# Core.net
KiCad netlist of a schematic drawn in Altium Designer
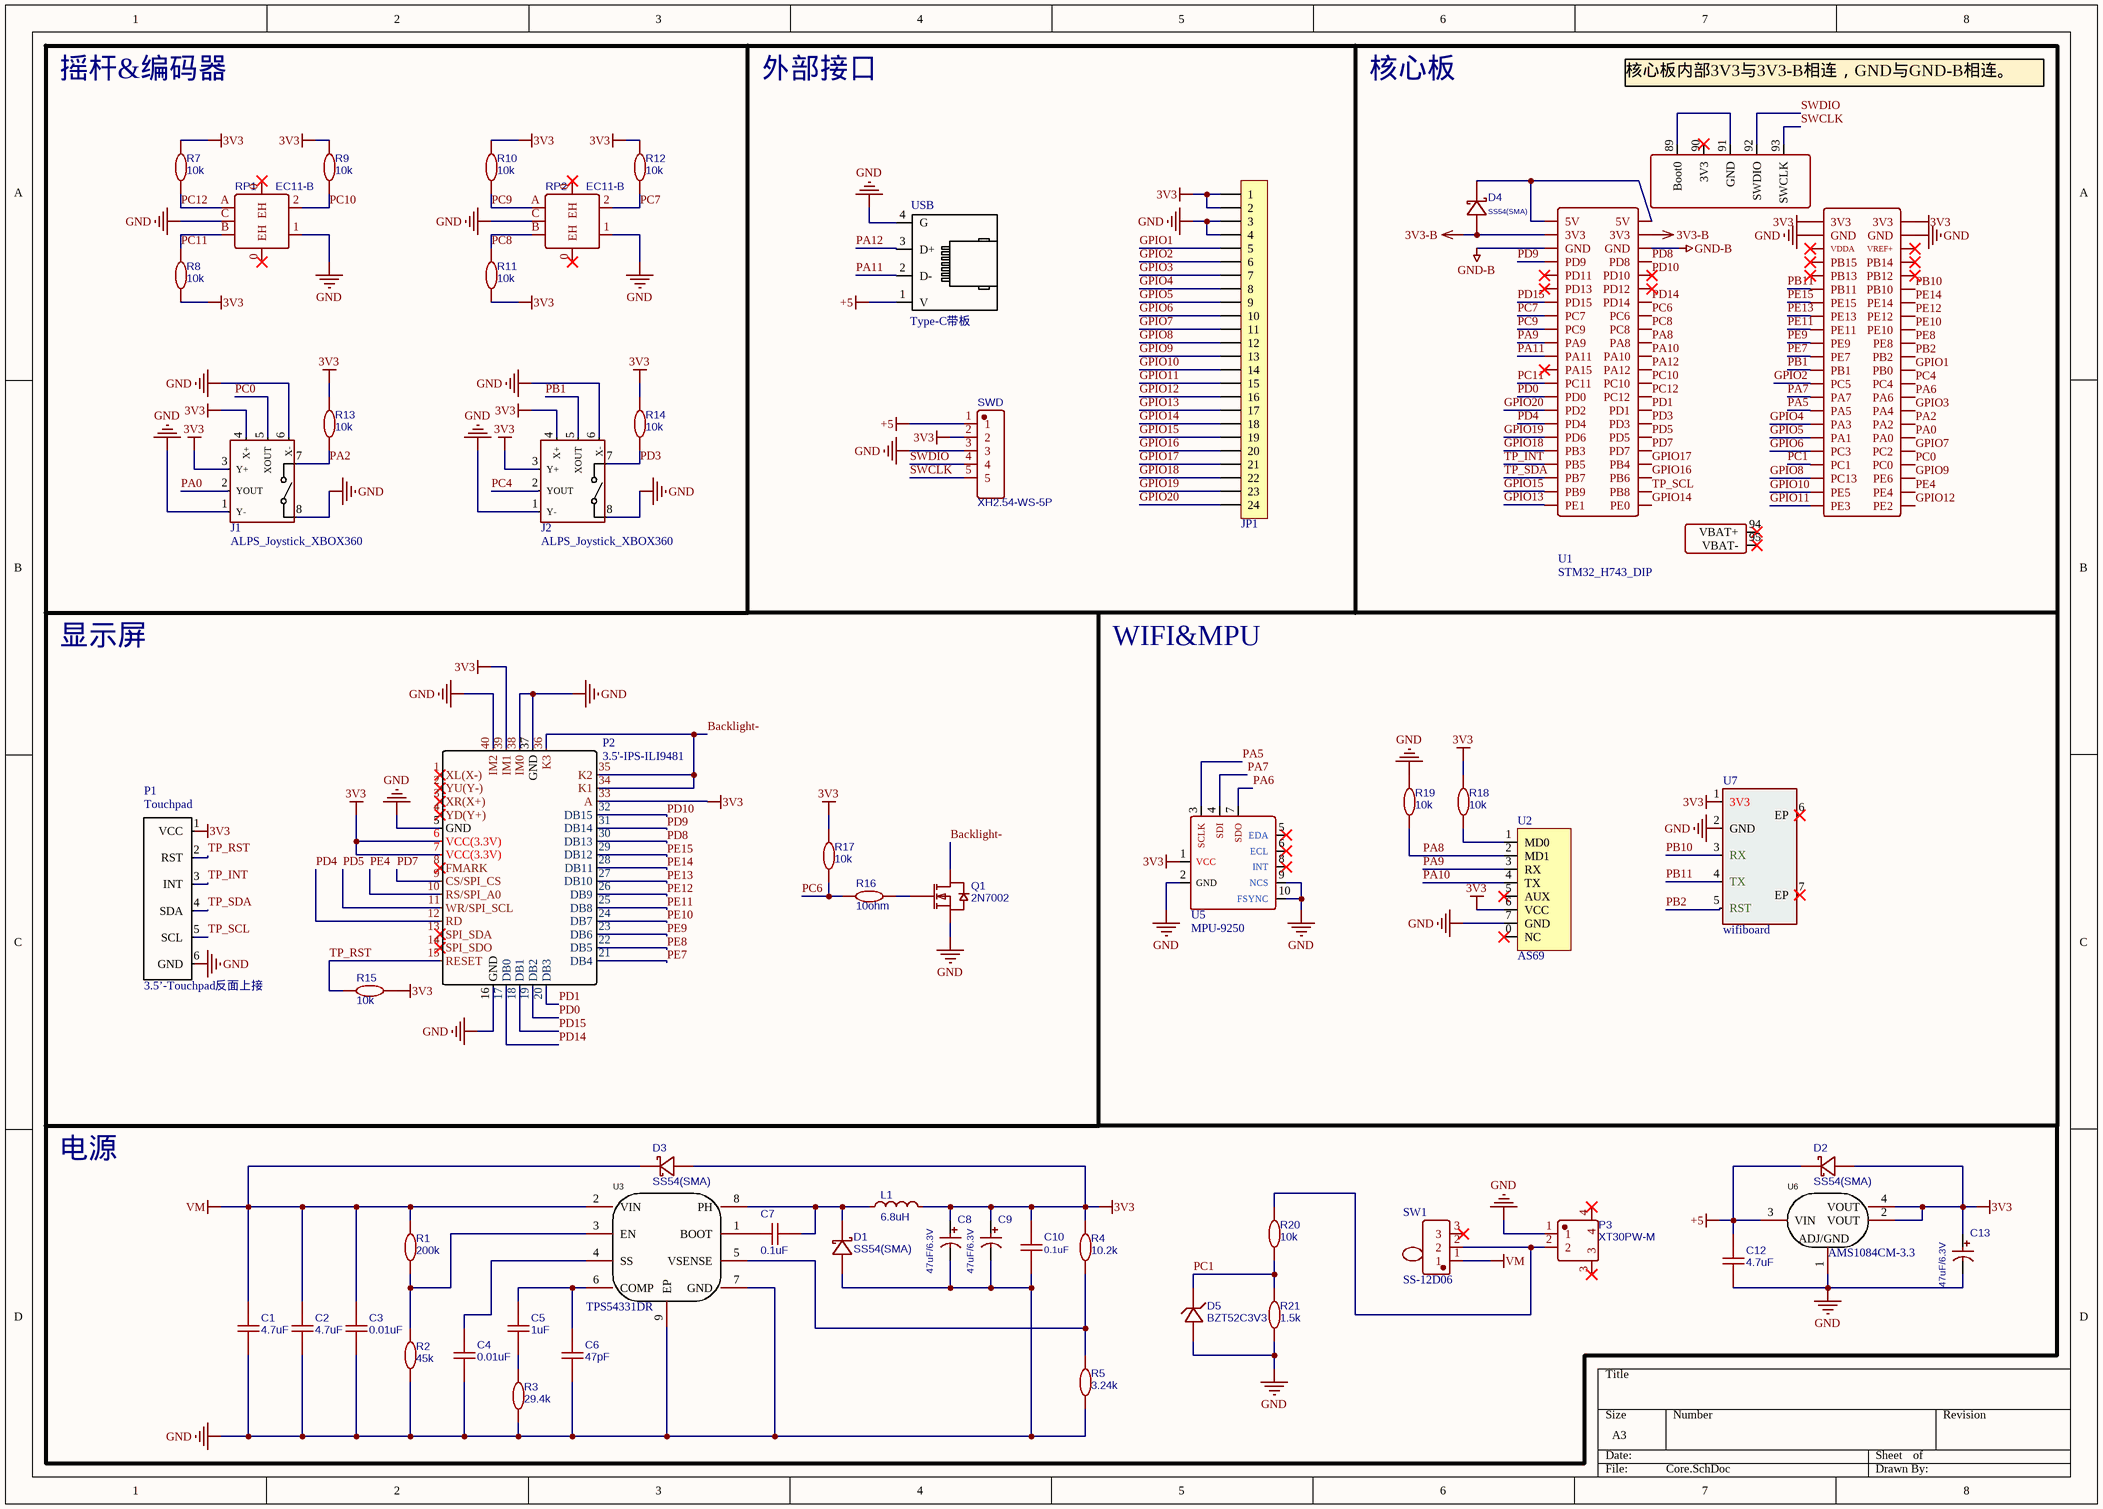
[diagram p0: Core.SchDoc]

(export (version "E")
  (design (tool "Eeschema 10.0.6"))
  (components
    (comp (ref "C1")
      (value "4.7uF")
      (footprint "C0805")
      (fields
        (field (name "BOM_SUPPLIER PART") "C476766")
        (field (name "BOM_MANUFACTURER PART") "C0805B104K500NT")
        (field (name "CONTRIBUTOR") "LCSC")
      )
      (libsource (lib "RC_schlib") (part "C0805"))
    )
    (comp (ref "C2")
      (value "4.7uF")
      (footprint "C0805")
      (fields
        (field (name "BOM_SUPPLIER PART") "C476766")
        (field (name "BOM_MANUFACTURER PART") "C0805B104K500NT")
        (field (name "CONTRIBUTOR") "LCSC")
      )
      (libsource (lib "RC_schlib") (part "C0805"))
    )
    (comp (ref "C3")
      (value "0.01uF")
      (footprint "C0603")
      (fields
        (field (name "BOM_MANUFACTURER PART") "CC0603KRX7R9BB104")
        (field (name "BOM_SUPPLIER PART") "C14663")
      )
      (libsource (lib "RC_schlib") (part "C0603"))
    )
    (comp (ref "C4")
      (value "0.01uF")
      (footprint "C0603")
      (fields
        (field (name "BOM_MANUFACTURER PART") "CC0603KRX7R9BB104")
        (field (name "BOM_SUPPLIER PART") "C14663")
      )
      (libsource (lib "RC_schlib") (part "C0603"))
    )
    (comp (ref "C5")
      (value "1uF")
      (footprint "C0603")
      (fields
        (field (name "BOM_MANUFACTURER PART") "CC0603KRX7R9BB104")
        (field (name "BOM_SUPPLIER PART") "C14663")
      )
      (libsource (lib "RC_schlib") (part "C0603"))
    )
    (comp (ref "C6")
      (value "47pF")
      (footprint "C0603")
      (fields
        (field (name "BOM_MANUFACTURER PART") "CC0603KRX7R9BB104")
        (field (name "BOM_SUPPLIER PART") "C14663")
      )
      (libsource (lib "RC_schlib") (part "C0603"))
    )
    (comp (ref "C7")
      (value "0.1uF")
      (footprint "C0603")
      (fields
        (field (name "BOM_MANUFACTURER PART") "CC0603KRX7R9BB104")
        (field (name "BOM_SUPPLIER PART") "C14663")
      )
      (libsource (lib "RC_schlib") (part "C0603"))
    )
    (comp (ref "C8")
      (value "47uF/6.3V")
      (footprint "CD A(3216)")
      (description "长3.2mm，宽1.6mm，厚1.6mm")
      (fields
        (field (name "BOM_MANUFACTURER PART") "50V 100uF 8X12")
        (field (name "BOM_SUPPLIER PART") "C2749")
      )
      (libsource (lib "eCap_schlib") (part "A型钽电容"))
    )
    (comp (ref "C9")
      (value "47uF/6.3V")
      (footprint "CD A(3216)")
      (description "长3.2mm，宽1.6mm，厚1.6mm")
      (fields
        (field (name "BOM_MANUFACTURER PART") "50V 100uF 8X12")
        (field (name "BOM_SUPPLIER PART") "C2749")
      )
      (libsource (lib "eCap_schlib") (part "A型钽电容"))
    )
    (comp (ref "C10")
      (value "0.1uF")
      (footprint "C0603")
      (fields
        (field (name "BOM_MANUFACTURER PART") "CC0603KRX7R9BB104")
        (field (name "BOM_SUPPLIER PART") "C14663")
      )
      (libsource (lib "RC_schlib") (part "C0603"))
    )
    (comp (ref "C12")
      (value "4.7uF")
      (footprint "C0805")
      (fields
        (field (name "BOM_SUPPLIER PART") "C476766")
        (field (name "BOM_MANUFACTURER PART") "C0805B104K500NT")
        (field (name "CONTRIBUTOR") "LCSC")
      )
      (libsource (lib "RC_schlib") (part "C0805"))
    )
    (comp (ref "C13")
      (value "47uF/6.3V")
      (footprint "CD A(3216)")
      (description "长3.2mm，宽1.6mm，厚1.6mm")
      (fields
        (field (name "BOM_MANUFACTURER PART") "50V 100uF 8X12")
        (field (name "BOM_SUPPLIER PART") "C2749")
      )
      (libsource (lib "eCap_schlib") (part "A型钽电容"))
    )
    (comp (ref "D1")
      (value "SS54(SMA)")
      (footprint "SMA")
      (fields
        (field (name "BOM_SUPPLIER PART") "C2931787")
        (field (name "BOM_MANUFACTURER PART") "SS34")
        (field (name "CONTRIBUTOR") "LCSC")
      )
      (libsource (lib "Diode_schlib") (part "SS54(SMA)"))
    )
    (comp (ref "D2")
      (value "SS54(SMA)")
      (footprint "SMA")
      (fields
        (field (name "BOM_SUPPLIER PART") "C2931787")
        (field (name "BOM_MANUFACTURER PART") "SS34")
        (field (name "CONTRIBUTOR") "LCSC")
      )
      (libsource (lib "Diode_schlib") (part "SS54(SMA)"))
    )
    (comp (ref "D3")
      (value "SS54(SMA)")
      (footprint "SMA")
      (fields
        (field (name "BOM_SUPPLIER PART") "C2931787")
        (field (name "BOM_MANUFACTURER PART") "SS34")
        (field (name "CONTRIBUTOR") "LCSC")
      )
      (libsource (lib "Diode_schlib") (part "SS54(SMA)"))
    )
    (comp (ref "D4")
      (value "SS54(SMA)")
      (footprint "SMA")
      (fields
        (field (name "BOM_SUPPLIER PART") "C2931787")
        (field (name "BOM_MANUFACTURER PART") "SS34")
        (field (name "CONTRIBUTOR") "LCSC")
      )
      (libsource (lib "Diode_schlib") (part "SS54(SMA)"))
    )
    (comp (ref "D5")
      (value "BZT52C3V3")
      (footprint "SOD-123")
      (fields (field (name "BOM_SUPPLIER PART") "C353528") (field (name "CONTRIBUTOR") "LCSC"))
      (libsource (lib "Diode_schlib") (part "BZT52C3V3"))
    )
    (comp (ref "J1")
      (value "ALPS_Joystick_XBOX360")
      (footprint "ALPS_Joystick_XBOX360")
      (libsource (lib "Joystick&Screen") (part "ALPS_Joystick_XBOX360"))
    )
    (comp (ref "J2")
      (value "ALPS_Joystick_XBOX360")
      (footprint "ALPS_Joystick_XBOX360")
      (libsource (lib "Joystick&Screen") (part "ALPS_Joystick_XBOX360"))
    )
    (comp (ref "JP1")
      (value "FPC1.0-24P")
      (footprint "FPC1.0-2H-WS-24P")
      (description "FPC连接器")
      (fields (field (name "版权归属") "黎明电子style"))
      (libsource (lib "FPC_schlib") (part "FPC-24P-1.0"))
    )
    (comp (ref "L1")
      (value "6.8uH")
      (footprint "IND-SMD_L4.9-W4.4_MAPM0420F")
      (fields
        (field (name "BOM_SUPPLIER PART") "C2936653")
        (field (name "BOM_MANUFACTURER PART") "HA42-4R7MT")
        (field (name "CONTRIBUTOR") "LCSC")
      )
      (libsource (lib "Inductance_schlib") (part "0420功率电感"))
    )
    (comp (ref "P1")
      (value "3.5’-Touchpad反面上接")
      (footprint "3.5‘-Touchpad反面上接")
      (libsource (lib "Joystick&Screen") (part "3.5’-Touchpad反面上接"))
    )
    (comp (ref "P2")
      (value "3.5'-IPS-ILI9481")
      (footprint "3.5'-IPS-ILI9481反面上接")
      (libsource (lib "Joystick&Screen") (part "3.5'-IPS-ILI9481反面上接"))
    )
    (comp (ref "P3")
      (value "XT30PW-M")
      (footprint "CONN-TH_XT30PW-M")
      (fields (field (name "BOM_SUPPLIER PART") "C431092") (field (name "CONTRIBUTOR") "LCSC"))
      (libsource (lib "AMASS_schlib") (part "XT30PW-M"))
    )
    (comp (ref "Q1")
      (value "2N7002")
      (footprint "SOT-23-3_L2.9-W1.3-P0.95-LS2.4-BR")
      (fields (field (name "BOM_SUPPLIER PART") "C8545"))
      (libsource (lib "MOSFET_schlib") (part "2N7002"))
    )
    (comp (ref "R1")
      (value "200k")
      (footprint "R0603")
      (fields
        (field (name "BOM_SUPPLIER PART") "C326890")
        (field (name "BOM_MANUFACTURER PART") "SR0603JR-071RL")
        (field (name "CONTRIBUTOR") "LCSC")
      )
      (libsource (lib "RC_schlib") (part "R0603"))
    )
    (comp (ref "R2")
      (value "45k")
      (footprint "R0603")
      (fields
        (field (name "BOM_SUPPLIER PART") "C326890")
        (field (name "BOM_MANUFACTURER PART") "SR0603JR-071RL")
        (field (name "CONTRIBUTOR") "LCSC")
      )
      (libsource (lib "RC_schlib") (part "R0603"))
    )
    (comp (ref "R3")
      (value "29.4k")
      (footprint "R0603")
      (fields
        (field (name "BOM_SUPPLIER PART") "C326890")
        (field (name "BOM_MANUFACTURER PART") "SR0603JR-071RL")
        (field (name "CONTRIBUTOR") "LCSC")
      )
      (libsource (lib "RC_schlib") (part "R0603"))
    )
    (comp (ref "R4")
      (value "10.2k")
      (footprint "R0603")
      (fields
        (field (name "BOM_SUPPLIER PART") "C326890")
        (field (name "BOM_MANUFACTURER PART") "SR0603JR-071RL")
        (field (name "CONTRIBUTOR") "LCSC")
      )
      (libsource (lib "RC_schlib") (part "R0603"))
    )
    (comp (ref "R5")
      (value "3.24k")
      (footprint "R0603")
      (fields
        (field (name "BOM_SUPPLIER PART") "C326890")
        (field (name "BOM_MANUFACTURER PART") "SR0603JR-071RL")
        (field (name "CONTRIBUTOR") "LCSC")
      )
      (libsource (lib "RC_schlib") (part "R0603"))
    )
    (comp (ref "R7")
      (value "10k")
      (footprint "R0603")
      (fields
        (field (name "BOM_SUPPLIER PART") "C326890")
        (field (name "BOM_MANUFACTURER PART") "SR0603JR-071RL")
        (field (name "CONTRIBUTOR") "LCSC")
      )
      (libsource (lib "RC_schlib") (part "R0603"))
    )
    (comp (ref "R8")
      (value "10k")
      (footprint "R0603")
      (fields
        (field (name "BOM_SUPPLIER PART") "C326890")
        (field (name "BOM_MANUFACTURER PART") "SR0603JR-071RL")
        (field (name "CONTRIBUTOR") "LCSC")
      )
      (libsource (lib "RC_schlib") (part "R0603"))
    )
    (comp (ref "R9")
      (value "10k")
      (footprint "R0603")
      (fields
        (field (name "BOM_SUPPLIER PART") "C326890")
        (field (name "BOM_MANUFACTURER PART") "SR0603JR-071RL")
        (field (name "CONTRIBUTOR") "LCSC")
      )
      (libsource (lib "RC_schlib") (part "R0603"))
    )
    (comp (ref "R10")
      (value "10k")
      (footprint "R0603")
      (fields
        (field (name "BOM_SUPPLIER PART") "C326890")
        (field (name "BOM_MANUFACTURER PART") "SR0603JR-071RL")
        (field (name "CONTRIBUTOR") "LCSC")
      )
      (libsource (lib "RC_schlib") (part "R0603"))
    )
    (comp (ref "R11")
      (value "10k")
      (footprint "R0603")
      (fields
        (field (name "BOM_SUPPLIER PART") "C326890")
        (field (name "BOM_MANUFACTURER PART") "SR0603JR-071RL")
        (field (name "CONTRIBUTOR") "LCSC")
      )
      (libsource (lib "RC_schlib") (part "R0603"))
    )
    (comp (ref "R12")
      (value "10k")
      (footprint "R0603")
      (fields
        (field (name "BOM_SUPPLIER PART") "C326890")
        (field (name "BOM_MANUFACTURER PART") "SR0603JR-071RL")
        (field (name "CONTRIBUTOR") "LCSC")
      )
      (libsource (lib "RC_schlib") (part "R0603"))
    )
    (comp (ref "R13")
      (value "10k")
      (footprint "R0603")
      (fields
        (field (name "BOM_SUPPLIER PART") "C326890")
        (field (name "BOM_MANUFACTURER PART") "SR0603JR-071RL")
        (field (name "CONTRIBUTOR") "LCSC")
      )
      (libsource (lib "RC_schlib") (part "R0603"))
    )
    (comp (ref "R14")
      (value "10k")
      (footprint "R0603")
      (fields
        (field (name "BOM_SUPPLIER PART") "C326890")
        (field (name "BOM_MANUFACTURER PART") "SR0603JR-071RL")
        (field (name "CONTRIBUTOR") "LCSC")
      )
      (libsource (lib "RC_schlib") (part "R0603"))
    )
    (comp (ref "R15")
      (value "10k")
      (footprint "R0603")
      (fields
        (field (name "BOM_SUPPLIER PART") "C326890")
        (field (name "BOM_MANUFACTURER PART") "SR0603JR-071RL")
        (field (name "CONTRIBUTOR") "LCSC")
      )
      (libsource (lib "RC_schlib") (part "R0603"))
    )
    (comp (ref "R16")
      (value "10ohm")
      (footprint "R0603")
      (fields
        (field (name "BOM_SUPPLIER PART") "C326890")
        (field (name "BOM_MANUFACTURER PART") "SR0603JR-071RL")
        (field (name "CONTRIBUTOR") "LCSC")
      )
      (libsource (lib "RC_schlib") (part "R0603"))
    )
    (comp (ref "R17")
      (value "10k")
      (footprint "R0603")
      (fields
        (field (name "BOM_SUPPLIER PART") "C326890")
        (field (name "BOM_MANUFACTURER PART") "SR0603JR-071RL")
        (field (name "CONTRIBUTOR") "LCSC")
      )
      (libsource (lib "RC_schlib") (part "R0603"))
    )
    (comp (ref "R18")
      (value "10k")
      (footprint "R0603")
      (fields
        (field (name "BOM_SUPPLIER PART") "C326890")
        (field (name "BOM_MANUFACTURER PART") "SR0603JR-071RL")
        (field (name "CONTRIBUTOR") "LCSC")
      )
      (libsource (lib "RC_schlib") (part "R0603"))
    )
    (comp (ref "R19")
      (value "10k")
      (footprint "R0603")
      (fields
        (field (name "BOM_SUPPLIER PART") "C326890")
        (field (name "BOM_MANUFACTURER PART") "SR0603JR-071RL")
        (field (name "CONTRIBUTOR") "LCSC")
      )
      (libsource (lib "RC_schlib") (part "R0603"))
    )
    (comp (ref "R20")
      (value "10k")
      (footprint "R0603")
      (fields
        (field (name "BOM_SUPPLIER PART") "C326890")
        (field (name "BOM_MANUFACTURER PART") "SR0603JR-071RL")
        (field (name "CONTRIBUTOR") "LCSC")
      )
      (libsource (lib "RC_schlib") (part "R0603"))
    )
    (comp (ref "R21")
      (value "1.5k")
      (footprint "R0603")
      (fields
        (field (name "BOM_SUPPLIER PART") "C326890")
        (field (name "BOM_MANUFACTURER PART") "SR0603JR-071RL")
        (field (name "CONTRIBUTOR") "LCSC")
      )
      (libsource (lib "RC_schlib") (part "R0603"))
    )
    (comp (ref "RP1")
      (value "EC11-B")
      (footprint "EC11-B")
      (description "数字开关编码器")
      (fields
        (field (name "BOM_SUPPLIER PART") "C118948")
        (field (name "BOM_MANUFACTURER PART") "3006P-1-102")
        (field (name "CONTRIBUTOR") "LCSC")
      )
      (libsource (lib "Potentiometer_schlib") (part "EC11-B"))
    )
    (comp (ref "RP2")
      (value "EC11-B")
      (footprint "EC11-B")
      (description "数字开关编码器")
      (fields
        (field (name "BOM_SUPPLIER PART") "C118948")
        (field (name "BOM_MANUFACTURER PART") "3006P-1-102")
        (field (name "CONTRIBUTOR") "LCSC")
      )
      (libsource (lib "Potentiometer_schlib") (part "EC11-B"))
    )
    (comp (ref "SW1")
      (value "SS-12D06")
      (footprint "SS-12D06")
      (description "卧式三脚拨动开关")
      (libsource (lib "Switch_schlib") (part "SS-12D06"))
    )
    (comp (ref "SWD")
      (value "XH2.54-WS-5P")
      (footprint "XH2.54-WS-5P")
      (description "贴片卧式XH接头")
      (fields
        (field (name "BOM_SUPPLIER PART") "C2905432")
        (field (name "BOM_MANUFACTURER PART") "KH-2.54PH90-1X18P-L13.8")
        (field (name "CONTRIBUTOR") "LCSC")
      )
      (libsource (lib "XH2.54_schlib") (part "XH2.54-WS-5P"))
    )
    (comp (ref "U1")
      (value "STM32_H743_DIP")
      (footprint "STM32_H743_DIP")
      (libsource (lib "STM32_H743") (part "STM32_H743_DIP"))
    )
    (comp (ref "U2")
      (value "AS69")
      (footprint "AS69")
      (description "常用串口模块")
      (libsource (lib "IC_schlib") (part "AS69"))
    )
    (comp (ref "U3")
      (value "TPS54331DR")
      (footprint "SOIC-8(with PowerPad)")
      (description "28V输入3A电流DCDC芯片")
      (fields (field (name "MANUFACTURER") "TI(德州仪器)"))
      (libsource (lib "IC_schlib") (part "TPS54331DR"))
    )
    (comp (ref "U5")
      (value "MPU-9250")
      (footprint "MPU-9250")
      (libsource (lib "Joystick&Screen") (part "MPU-9250"))
    )
    (comp (ref "U6")
      (value "AMS1084CM-3.3")
      (footprint "TO-263-3L_L10.2-W8.7-P2.54-LS15.3-BL")
      (description "3.3V 5A")
      (fields (field (name "MANUFACTURER") "UMW(广东友台半导体)"))
      (libsource (lib "IC_schlib") (part "AMS1084CM-3.3"))
    )
    (comp (ref "U7")
      (value "wifiboard")
      (footprint "wifiboard")
      (libsource (lib "Joystick&Screen") (part "wifiboard"))
    )
    (comp (ref "USB") (value "Type-C带板") (footprint "Type-C母头带板") (libsource (lib "USB") (part "Type-C带板")))
  )
  (nets
    (net (code "1") (name "+5") (class "Default")
      (node (ref "C12") (pin "2") (pinfunction "2_2") (pintype "passive"))
      (node (ref "D2") (pin "2") (pinfunction "K_2") (pintype "passive"))
      (node (ref "SWD") (pin "1") (pinfunction "1_1") (pintype "passive"))
      (node (ref "U6") (pin "3") (pinfunction "VIN_3") (pintype "passive"))
      (node (ref "USB") (pin "1") (pinfunction "V_1") (pintype "passive"))
    )
    (net (code "2") (name "/Backlight-") (class "Default")
      (node (ref "P2") (pin "34") (pinfunction "K1_34") (pintype "passive"))
      (node (ref "P2") (pin "35") (pinfunction "K2_35") (pintype "passive"))
      (node (ref "P2") (pin "36") (pinfunction "K3_36") (pintype "passive"))
      (node (ref "Q1") (pin "3") (pinfunction "D_3") (pintype "passive"))
    )
    (net (code "3") (name "/GPIO1") (class "Default")
      (node (ref "JP1") (pin "5") (pinfunction "5_5") (pintype "passive"))
      (node (ref "U1") (pin "68") (pinfunction "PB0_68") (pintype "passive"))
    )
    (net (code "4") (name "/GPIO2") (class "Default")
      (node (ref "JP1") (pin "6") (pinfunction "6_6") (pintype "passive"))
      (node (ref "U1") (pin "69") (pinfunction "PC5_69") (pintype "passive"))
    )
    (net (code "5") (name "/GPIO3") (class "Default")
      (node (ref "JP1") (pin "7") (pinfunction "7_7") (pintype "passive"))
      (node (ref "U1") (pin "74") (pinfunction "PA4_74") (pintype "passive"))
    )
    (net (code "6") (name "/GPIO4") (class "Default")
      (node (ref "JP1") (pin "8") (pinfunction "8_8") (pintype "passive"))
      (node (ref "U1") (pin "75") (pinfunction "PA3_75") (pintype "passive"))
    )
    (net (code "7") (name "/GPIO5") (class "Default")
      (node (ref "JP1") (pin "9") (pinfunction "9_9") (pintype "passive"))
      (node (ref "U1") (pin "77") (pinfunction "PA1_77") (pintype "passive"))
    )
    (net (code "8") (name "/GPIO6") (class "Default")
      (node (ref "JP1") (pin "10") (pinfunction "10_10") (pintype "passive"))
      (node (ref "U1") (pin "79") (pinfunction "PC3_79") (pintype "passive"))
    )
    (net (code "9") (name "/GPIO7") (class "Default")
      (node (ref "JP1") (pin "11") (pinfunction "11_11") (pintype "passive"))
      (node (ref "U1") (pin "80") (pinfunction "PC2_80") (pintype "passive"))
    )
    (net (code "10") (name "/GPIO8") (class "Default")
      (node (ref "JP1") (pin "12") (pinfunction "12_12") (pintype "passive"))
      (node (ref "U1") (pin "83") (pinfunction "PC13_83") (pintype "passive"))
    )
    (net (code "11") (name "/GPIO9") (class "Default")
      (node (ref "JP1") (pin "13") (pinfunction "13_13") (pintype "passive"))
      (node (ref "U1") (pin "84") (pinfunction "PE6_84") (pintype "passive"))
    )
    (net (code "12") (name "/GPIO10") (class "Default")
      (node (ref "JP1") (pin "14") (pinfunction "14_14") (pintype "passive"))
      (node (ref "U1") (pin "85") (pinfunction "PE5_85") (pintype "passive"))
    )
    (net (code "13") (name "/GPIO11") (class "Default")
      (node (ref "JP1") (pin "15") (pinfunction "15_15") (pintype "passive"))
      (node (ref "U1") (pin "87") (pinfunction "PE3_87") (pintype "passive"))
    )
    (net (code "14") (name "/GPIO12") (class "Default")
      (node (ref "JP1") (pin "16") (pinfunction "16_16") (pintype "passive"))
      (node (ref "U1") (pin "88") (pinfunction "PE2_88") (pintype "passive"))
    )
    (net (code "15") (name "/GPIO13") (class "Default")
      (node (ref "JP1") (pin "17") (pinfunction "17_17") (pintype "passive"))
      (node (ref "U1") (pin "43") (pinfunction "PE1_43") (pintype "passive"))
    )
    (net (code "16") (name "/GPIO14") (class "Default")
      (node (ref "JP1") (pin "18") (pinfunction "18_18") (pintype "passive"))
      (node (ref "U1") (pin "44") (pinfunction "PE0_44") (pintype "passive"))
    )
    (net (code "17") (name "/GPIO15") (class "Default")
      (node (ref "JP1") (pin "19") (pinfunction "19_19") (pintype "passive"))
      (node (ref "U1") (pin "41") (pinfunction "PB9_41") (pintype "passive"))
    )
    (net (code "18") (name "/GPIO16") (class "Default")
      (node (ref "JP1") (pin "20") (pinfunction "20_20") (pintype "passive"))
      (node (ref "U1") (pin "40") (pinfunction "PB6_40") (pintype "passive"))
    )
    (net (code "19") (name "/GPIO17") (class "Default")
      (node (ref "JP1") (pin "21") (pinfunction "21_21") (pintype "passive"))
      (node (ref "U1") (pin "38") (pinfunction "PB4_38") (pintype "passive"))
    )
    (net (code "20") (name "/GPIO18") (class "Default")
      (node (ref "JP1") (pin "22") (pinfunction "22_22") (pintype "passive"))
      (node (ref "U1") (pin "35") (pinfunction "PB3_35") (pintype "passive"))
    )
    (net (code "21") (name "/GPIO19") (class "Default")
      (node (ref "JP1") (pin "23") (pinfunction "23_23") (pintype "passive"))
      (node (ref "U1") (pin "33") (pinfunction "PD6_33") (pintype "passive"))
    )
    (net (code "22") (name "/GPIO20") (class "Default")
      (node (ref "JP1") (pin "24") (pinfunction "24_24") (pintype "passive"))
      (node (ref "U1") (pin "29") (pinfunction "PD2_29") (pintype "passive"))
    )
    (net (code "23") (name "/PA0") (class "Default")
      (node (ref "J1") (pin "2") (pinfunction "YOUT_2") (pintype "passive"))
      (node (ref "U1") (pin "78") (pinfunction "PA0_78") (pintype "passive"))
    )
    (net (code "24") (name "/PA2") (class "Default")
      (node (ref "J1") (pin "7") (pinfunction "K1_7") (pintype "passive"))
      (node (ref "R13") (pin "2") (pinfunction "2_2") (pintype "passive"))
      (node (ref "U1") (pin "76") (pinfunction "PA2_76") (pintype "passive"))
    )
    (net (code "25") (name "/PA5") (class "Default")
      (node (ref "U1") (pin "73") (pinfunction "PA5_73") (pintype "passive"))
      (node (ref "U5") (pin "3") (pinfunction "SCLK_3") (pintype "passive"))
    )
    (net (code "26") (name "/PA6") (class "Default")
      (node (ref "U1") (pin "72") (pinfunction "PA6_72") (pintype "passive"))
      (node (ref "U5") (pin "7") (pinfunction "SDO_7") (pintype "passive"))
    )
    (net (code "27") (name "/PA7") (class "Default")
      (node (ref "U1") (pin "71") (pinfunction "PA7_71") (pintype "passive"))
      (node (ref "U5") (pin "4") (pinfunction "SDI_4") (pintype "passive"))
    )
    (net (code "28") (name "/PA8") (class "Default")
      (node (ref "R19") (pin "2") (pinfunction "2_2") (pintype "passive"))
      (node (ref "U1") (pin "20") (pinfunction "PA8_20") (pintype "passive"))
      (node (ref "U2") (pin "2") (pinfunction "MD1_2") (pintype "passive"))
    )
    (net (code "29") (name "/PA9") (class "Default")
      (node (ref "U1") (pin "19") (pinfunction "PA9_19") (pintype "passive"))
      (node (ref "U2") (pin "3") (pinfunction "RX_3") (pintype "passive"))
    )
    (net (code "30") (name "/PA10") (class "Default")
      (node (ref "U1") (pin "22") (pinfunction "PA10_22") (pintype "passive"))
      (node (ref "U2") (pin "4") (pinfunction "TX_4") (pintype "passive"))
    )
    (net (code "31") (name "/PA11") (class "Default")
      (node (ref "U1") (pin "21") (pinfunction "PA11_21") (pintype "passive"))
      (node (ref "USB") (pin "2") (pinfunction "D-_2") (pintype "passive"))
    )
    (net (code "32") (name "/PA12") (class "Default")
      (node (ref "U1") (pin "24") (pinfunction "PA12_24") (pintype "passive"))
      (node (ref "USB") (pin "3") (pinfunction "D+_3") (pintype "passive"))
    )
    (net (code "33") (name "/PB1") (class "Default")
      (node (ref "J2") (pin "5") (pinfunction "XOUT_5") (pintype "passive"))
      (node (ref "U1") (pin "67") (pinfunction "PB1_67") (pintype "passive"))
    )
    (net (code "34") (name "/PB2") (class "Default")
      (node (ref "U1") (pin "66") (pinfunction "PB2_66") (pintype "passive"))
      (node (ref "U7") (pin "5") (pinfunction "RST_5") (pintype "passive"))
    )
    (net (code "35") (name "/PB10") (class "Default")
      (node (ref "U1") (pin "56") (pinfunction "PB10_56") (pintype "passive"))
      (node (ref "U7") (pin "3") (pinfunction "RX_3") (pintype "passive"))
    )
    (net (code "36") (name "/PB11") (class "Default")
      (node (ref "U1") (pin "55") (pinfunction "PB11_55") (pintype "passive"))
      (node (ref "U7") (pin "4") (pinfunction "TX_4") (pintype "passive"))
    )
    (net (code "37") (name "/PC0") (class "Default")
      (node (ref "J1") (pin "5") (pinfunction "XOUT_5") (pintype "passive"))
      (node (ref "U1") (pin "82") (pinfunction "PC0_82") (pintype "passive"))
    )
    (net (code "38") (name "/PC1") (class "Default")
      (node (ref "D5") (pin "2") (pinfunction "C_2") (pintype "passive"))
      (node (ref "R20") (pin "2") (pinfunction "2_2") (pintype "passive"))
      (node (ref "R21") (pin "1") (pinfunction "1_1") (pintype "passive"))
      (node (ref "U1") (pin "81") (pinfunction "PC1_81") (pintype "passive"))
    )
    (net (code "39") (name "/PC4") (class "Default")
      (node (ref "J2") (pin "2") (pinfunction "YOUT_2") (pintype "passive"))
      (node (ref "U1") (pin "70") (pinfunction "PC4_70") (pintype "passive"))
    )
    (net (code "40") (name "/PC6") (class "Default")
      (node (ref "R16") (pin "1") (pinfunction "1_1") (pintype "passive"))
      (node (ref "R17") (pin "2") (pinfunction "2_2") (pintype "passive"))
      (node (ref "U1") (pin "16") (pinfunction "PC6_16") (pintype "passive"))
    )
    (net (code "41") (name "/PC7") (class "Default")
      (node (ref "R12") (pin "2") (pinfunction "2_2") (pintype "passive"))
      (node (ref "RP2") (pin "2") (pinfunction "2_2") (pintype "passive"))
      (node (ref "U1") (pin "15") (pinfunction "PC7_15") (pintype "passive"))
    )
    (net (code "42") (name "/PC8") (class "Default")
      (node (ref "R11") (pin "1") (pinfunction "1_1") (pintype "passive"))
      (node (ref "RP2") (pin "B") (pinfunction "B_B") (pintype "passive"))
      (node (ref "U1") (pin "18") (pinfunction "PC8_18") (pintype "passive"))
    )
    (net (code "43") (name "/PC9") (class "Default")
      (node (ref "R10") (pin "2") (pinfunction "2_2") (pintype "passive"))
      (node (ref "RP2") (pin "A") (pinfunction "A_A") (pintype "passive"))
      (node (ref "U1") (pin "17") (pinfunction "PC9_17") (pintype "passive"))
    )
    (net (code "44") (name "/PC10") (class "Default")
      (node (ref "R9") (pin "2") (pinfunction "2_2") (pintype "passive"))
      (node (ref "RP1") (pin "2") (pinfunction "2_2") (pintype "passive"))
      (node (ref "U1") (pin "26") (pinfunction "PC10_26") (pintype "passive"))
    )
    (net (code "45") (name "/PC11") (class "Default")
      (node (ref "R8") (pin "1") (pinfunction "1_1") (pintype "passive"))
      (node (ref "RP1") (pin "B") (pinfunction "B_B") (pintype "passive"))
      (node (ref "U1") (pin "25") (pinfunction "PC11_25") (pintype "passive"))
    )
    (net (code "46") (name "/PC12") (class "Default")
      (node (ref "R7") (pin "2") (pinfunction "2_2") (pintype "passive"))
      (node (ref "RP1") (pin "A") (pinfunction "A_A") (pintype "passive"))
      (node (ref "U1") (pin "28") (pinfunction "PC12_28") (pintype "passive"))
    )
    (net (code "47") (name "/PD0") (class "Default")
      (node (ref "P2") (pin "19") (pinfunction "DB2_19") (pintype "passive"))
      (node (ref "U1") (pin "27") (pinfunction "PD0_27") (pintype "passive"))
    )
    (net (code "48") (name "/PD1") (class "Default")
      (node (ref "P2") (pin "20") (pinfunction "DB3_20") (pintype "passive"))
      (node (ref "U1") (pin "30") (pinfunction "PD1_30") (pintype "passive"))
    )
    (net (code "49") (name "/PD3") (class "Default")
      (node (ref "J2") (pin "7") (pinfunction "K1_7") (pintype "passive"))
      (node (ref "R14") (pin "2") (pinfunction "2_2") (pintype "passive"))
      (node (ref "U1") (pin "32") (pinfunction "PD3_32") (pintype "passive"))
    )
    (net (code "50") (name "/PD4") (class "Default")
      (node (ref "P2") (pin "12") (pinfunction "RD_12") (pintype "passive"))
      (node (ref "U1") (pin "31") (pinfunction "PD4_31") (pintype "passive"))
    )
    (net (code "51") (name "/PD5") (class "Default")
      (node (ref "P2") (pin "11") (pinfunction "WR/SPI_SCL_11") (pintype "passive"))
      (node (ref "U1") (pin "34") (pinfunction "PD5_34") (pintype "passive"))
    )
    (net (code "52") (name "/PD7") (class "Default")
      (node (ref "P2") (pin "9") (pinfunction "CS/SPI_CS_9") (pintype "passive"))
      (node (ref "U1") (pin "36") (pinfunction "PD7_36") (pintype "passive"))
    )
    (net (code "53") (name "/PD8") (class "Default")
      (node (ref "P2") (pin "30") (pinfunction "DB13_30") (pintype "passive"))
      (node (ref "U1") (pin "8") (pinfunction "PD8_8") (pintype "passive"))
    )
    (net (code "54") (name "/PD9") (class "Default")
      (node (ref "P2") (pin "31") (pinfunction "DB14_31") (pintype "passive"))
      (node (ref "U1") (pin "7") (pinfunction "PD9_7") (pintype "passive"))
    )
    (net (code "55") (name "/PD10") (class "Default")
      (node (ref "P2") (pin "32") (pinfunction "DB15_32") (pintype "passive"))
      (node (ref "U1") (pin "10") (pinfunction "PD10_10") (pintype "passive"))
    )
    (net (code "56") (name "/PD14") (class "Default")
      (node (ref "P2") (pin "17") (pinfunction "DB0_17") (pintype "passive"))
      (node (ref "U1") (pin "14") (pinfunction "PD14_14") (pintype "passive"))
    )
    (net (code "57") (name "/PD15") (class "Default")
      (node (ref "P2") (pin "18") (pinfunction "DB1_18") (pintype "passive"))
      (node (ref "U1") (pin "13") (pinfunction "PD15_13") (pintype "passive"))
    )
    (net (code "58") (name "/PE4") (class "Default")
      (node (ref "P2") (pin "10") (pinfunction "RS/SPI_A0_10") (pintype "passive"))
      (node (ref "U1") (pin "86") (pinfunction "PE4_86") (pintype "passive"))
    )
    (net (code "59") (name "/PE7") (class "Default")
      (node (ref "P2") (pin "21") (pinfunction "DB4_21") (pintype "passive"))
      (node (ref "U1") (pin "65") (pinfunction "PE7_65") (pintype "passive"))
    )
    (net (code "60") (name "/PE8") (class "Default")
      (node (ref "P2") (pin "22") (pinfunction "DB5_22") (pintype "passive"))
      (node (ref "U1") (pin "64") (pinfunction "PE8_64") (pintype "passive"))
    )
    (net (code "61") (name "/PE9") (class "Default")
      (node (ref "P2") (pin "23") (pinfunction "DB6_23") (pintype "passive"))
      (node (ref "U1") (pin "63") (pinfunction "PE9_63") (pintype "passive"))
    )
    (net (code "62") (name "/PE10") (class "Default")
      (node (ref "P2") (pin "24") (pinfunction "DB7_24") (pintype "passive"))
      (node (ref "U1") (pin "62") (pinfunction "PE10_62") (pintype "passive"))
    )
    (net (code "63") (name "/PE11") (class "Default")
      (node (ref "P2") (pin "25") (pinfunction "DB8_25") (pintype "passive"))
      (node (ref "U1") (pin "61") (pinfunction "PE11_61") (pintype "passive"))
    )
    (net (code "64") (name "/PE12") (class "Default")
      (node (ref "P2") (pin "26") (pinfunction "DB9_26") (pintype "passive"))
      (node (ref "U1") (pin "60") (pinfunction "PE12_60") (pintype "passive"))
    )
    (net (code "65") (name "/PE13") (class "Default")
      (node (ref "P2") (pin "27") (pinfunction "DB10_27") (pintype "passive"))
      (node (ref "U1") (pin "59") (pinfunction "PE13_59") (pintype "passive"))
    )
    (net (code "66") (name "/PE14") (class "Default")
      (node (ref "P2") (pin "28") (pinfunction "DB11_28") (pintype "passive"))
      (node (ref "U1") (pin "58") (pinfunction "PE14_58") (pintype "passive"))
    )
    (net (code "67") (name "/PE15") (class "Default")
      (node (ref "P2") (pin "29") (pinfunction "DB12_29") (pintype "passive"))
      (node (ref "U1") (pin "57") (pinfunction "PE15_57") (pintype "passive"))
    )
    (net (code "68") (name "/SWCLK") (class "Default")
      (node (ref "SWD") (pin "5") (pinfunction "5_5") (pintype "passive"))
      (node (ref "U1") (pin "93") (pinfunction "SWCLK_93") (pintype "passive"))
    )
    (net (code "69") (name "/SWDIO") (class "Default")
      (node (ref "SWD") (pin "4") (pinfunction "4_4") (pintype "passive"))
      (node (ref "U1") (pin "92") (pinfunction "SWDIO_92") (pintype "passive"))
    )
    (net (code "70") (name "/TP_INT") (class "Default")
      (node (ref "P1") (pin "3") (pinfunction "INT_3") (pintype "passive"))
      (node (ref "U1") (pin "37") (pinfunction "PB5_37") (pintype "passive"))
    )
    (net (code "71") (name "/TP_RST") (class "Default")
      (node (ref "P1") (pin "2") (pinfunction "RST_2") (pintype "passive"))
      (node (ref "P2") (pin "15") (pinfunction "RESET_15") (pintype "passive"))
      (node (ref "R15") (pin "1") (pinfunction "1_1") (pintype "passive"))
    )
    (net (code "72") (name "/TP_SCL") (class "Default")
      (node (ref "P1") (pin "5") (pinfunction "SCL_5") (pintype "passive"))
      (node (ref "U1") (pin "42") (pinfunction "PB8_42") (pintype "passive"))
    )
    (net (code "73") (name "/TP_SDA") (class "Default")
      (node (ref "P1") (pin "4") (pinfunction "SDA_4") (pintype "passive"))
      (node (ref "U1") (pin "39") (pinfunction "PB7_39") (pintype "passive"))
    )
    (net (code "74") (name "3V3") (class "Default")
      (node (ref "C10") (pin "1") (pinfunction "1_1") (pintype "passive"))
      (node (ref "C13") (pin "1") (pinfunction "1_1") (pintype "passive"))
      (node (ref "C8") (pin "1") (pinfunction "1_1") (pintype "passive"))
      (node (ref "C9") (pin "1") (pinfunction "1_1") (pintype "passive"))
      (node (ref "D2") (pin "1") (pinfunction "A_1") (pintype "passive"))
      (node (ref "D3") (pin "1") (pinfunction "A_1") (pintype "passive"))
      (node (ref "J1") (pin "3") (pinfunction "Y+_3") (pintype "passive"))
      (node (ref "J1") (pin "4") (pinfunction "X+_4") (pintype "passive"))
      (node (ref "J2") (pin "3") (pinfunction "Y+_3") (pintype "passive"))
      (node (ref "J2") (pin "4") (pinfunction "X+_4") (pintype "passive"))
      (node (ref "JP1") (pin "1") (pinfunction "1_1") (pintype "passive"))
      (node (ref "JP1") (pin "2") (pinfunction "2_2") (pintype "passive"))
      (node (ref "L1") (pin "2") (pinfunction "2_2") (pintype "passive"))
      (node (ref "P1") (pin "1") (pinfunction "VCC_1") (pintype "passive"))
      (node (ref "P2") (pin "33") (pinfunction "A_33") (pintype "passive"))
      (node (ref "P2") (pin "39") (pinfunction "IM1_39") (pintype "passive"))
      (node (ref "P2") (pin "6") (pinfunction "VCC(3.3V)_6") (pintype "passive"))
      (node (ref "P2") (pin "7") (pinfunction "VCC(3.3V)_7") (pintype "passive"))
      (node (ref "R10") (pin "1") (pinfunction "1_1") (pintype "passive"))
      (node (ref "R11") (pin "2") (pinfunction "2_2") (pintype "passive"))
      (node (ref "R12") (pin "1") (pinfunction "1_1") (pintype "passive"))
      (node (ref "R13") (pin "1") (pinfunction "1_1") (pintype "passive"))
      (node (ref "R14") (pin "1") (pinfunction "1_1") (pintype "passive"))
      (node (ref "R15") (pin "2") (pinfunction "2_2") (pintype "passive"))
      (node (ref "R17") (pin "1") (pinfunction "1_1") (pintype "passive"))
      (node (ref "R18") (pin "1") (pinfunction "1_1") (pintype "passive"))
      (node (ref "R4") (pin "2") (pinfunction "2_2") (pintype "passive"))
      (node (ref "R7") (pin "1") (pinfunction "1_1") (pintype "passive"))
      (node (ref "R8") (pin "2") (pinfunction "2_2") (pintype "passive"))
      (node (ref "R9") (pin "1") (pinfunction "1_1") (pintype "passive"))
      (node (ref "SWD") (pin "2") (pinfunction "2_2") (pintype "passive"))
      (node (ref "U1") (pin "45") (pinfunction "3V3_45") (pintype "passive"))
      (node (ref "U1") (pin "46") (pinfunction "3V3_46") (pintype "passive"))
      (node (ref "U2") (pin "6") (pinfunction "VCC_6") (pintype "passive"))
      (node (ref "U5") (pin "1") (pinfunction "VCC_1") (pintype "passive"))
      (node (ref "U6") (pin "2") (pinfunction "VOUT_2") (pintype "passive"))
      (node (ref "U6") (pin "4") (pinfunction "VOUT_4") (pintype "passive"))
      (node (ref "U7") (pin "1") (pinfunction "3V3_1") (pintype "passive"))
    )
    (net (code "75") (name "3V3-B") (class "Default")
      (node (ref "D4") (pin "1") (pinfunction "A_1") (pintype "passive"))
      (node (ref "U1") (pin "3") (pinfunction "3V3_3") (pintype "passive"))
      (node (ref "U1") (pin "4") (pinfunction "3V3_4") (pintype "passive"))
    )
    (net (code "76") (name "GND") (class "Default")
      (node (ref "C1") (pin "1") (pinfunction "1_1") (pintype "passive"))
      (node (ref "C10") (pin "2") (pinfunction "2_2") (pintype "passive"))
      (node (ref "C12") (pin "1") (pinfunction "1_1") (pintype "passive"))
      (node (ref "C13") (pin "2") (pinfunction "2_2") (pintype "passive"))
      (node (ref "C2") (pin "1") (pinfunction "1_1") (pintype "passive"))
      (node (ref "C3") (pin "1") (pinfunction "1_1") (pintype "passive"))
      (node (ref "C4") (pin "1") (pinfunction "1_1") (pintype "passive"))
      (node (ref "C6") (pin "1") (pinfunction "1_1") (pintype "passive"))
      (node (ref "C8") (pin "2") (pinfunction "2_2") (pintype "passive"))
      (node (ref "C9") (pin "2") (pinfunction "2_2") (pintype "passive"))
      (node (ref "D1") (pin "1") (pinfunction "A_1") (pintype "passive"))
      (node (ref "D5") (pin "1") (pinfunction "A_1") (pintype "passive"))
      (node (ref "J1") (pin "1") (pinfunction "Y-_1") (pintype "passive"))
      (node (ref "J1") (pin "6") (pinfunction "X-_6") (pintype "passive"))
      (node (ref "J1") (pin "8") (pinfunction "K2_8") (pintype "passive"))
      (node (ref "J2") (pin "1") (pinfunction "Y-_1") (pintype "passive"))
      (node (ref "J2") (pin "6") (pinfunction "X-_6") (pintype "passive"))
      (node (ref "J2") (pin "8") (pinfunction "K2_8") (pintype "passive"))
      (node (ref "JP1") (pin "3") (pinfunction "3_3") (pintype "passive"))
      (node (ref "JP1") (pin "4") (pinfunction "4_4") (pintype "passive"))
      (node (ref "P1") (pin "6") (pinfunction "GND_6") (pintype "passive"))
      (node (ref "P2") (pin "16") (pinfunction "GND_16") (pintype "passive"))
      (node (ref "P2") (pin "37") (pinfunction "GND_37") (pintype "passive"))
      (node (ref "P2") (pin "38") (pinfunction "IM0_38") (pintype "passive"))
      (node (ref "P2") (pin "40") (pinfunction "IM2_40") (pintype "passive"))
      (node (ref "P2") (pin "5") (pinfunction "GND_5") (pintype "passive"))
      (node (ref "P3") (pin "1") (pinfunction "1_1") (pintype "passive"))
      (node (ref "Q1") (pin "2") (pinfunction "S_2") (pintype "passive"))
      (node (ref "R19") (pin "1") (pinfunction "1_1") (pintype "passive"))
      (node (ref "R2") (pin "1") (pinfunction "1_1") (pintype "passive"))
      (node (ref "R21") (pin "2") (pinfunction "2_2") (pintype "passive"))
      (node (ref "R3") (pin "1") (pinfunction "1_1") (pintype "passive"))
      (node (ref "R5") (pin "1") (pinfunction "1_1") (pintype "passive"))
      (node (ref "RP1") (pin "1") (pinfunction "1_1") (pintype "passive"))
      (node (ref "RP1") (pin "C") (pinfunction "C_C") (pintype "passive"))
      (node (ref "RP2") (pin "1") (pinfunction "1_1") (pintype "passive"))
      (node (ref "RP2") (pin "C") (pinfunction "C_C") (pintype "passive"))
      (node (ref "SWD") (pin "3") (pinfunction "3_3") (pintype "passive"))
      (node (ref "U1") (pin "47") (pinfunction "GND_47") (pintype "passive"))
      (node (ref "U1") (pin "48") (pinfunction "GND_48") (pintype "passive"))
      (node (ref "U2") (pin "7") (pinfunction "GND_7") (pintype "passive"))
      (node (ref "U3") (pin "7") (pinfunction "GND_7") (pintype "passive"))
      (node (ref "U3") (pin "9") (pinfunction "EP_9") (pintype "passive"))
      (node (ref "U5") (pin "10") (pinfunction "FSYNC_10") (pintype "passive"))
      (node (ref "U5") (pin "2") (pinfunction "GND_2") (pintype "passive"))
      (node (ref "U5") (pin "9") (pinfunction "NCS_9") (pintype "passive"))
      (node (ref "U6") (pin "1") (pinfunction "ADJ/GND_1") (pintype "passive"))
      (node (ref "U7") (pin "2") (pinfunction "GND_2") (pintype "passive"))
      (node (ref "USB") (pin "4") (pinfunction "G_4") (pintype "passive"))
    )
    (net (code "77") (name "GND-B") (class "Default")
      (node (ref "U1") (pin "5") (pinfunction "GND_5") (pintype "passive"))
      (node (ref "U1") (pin "6") (pinfunction "GND_6") (pintype "passive"))
    )
    (net (code "78") (name "Net-(C5-Pad1)") (class "Default")
      (node (ref "C5") (pin "1") (pinfunction "1_1") (pintype "passive"))
      (node (ref "R3") (pin "2") (pinfunction "2_2") (pintype "passive"))
    )
    (net (code "79") (name "Net-(D1-K)") (class "Default")
      (node (ref "C7") (pin "1") (pinfunction "1_1") (pintype "passive"))
      (node (ref "D1") (pin "2") (pinfunction "K_2") (pintype "passive"))
      (node (ref "L1") (pin "1") (pinfunction "1_1") (pintype "passive"))
      (node (ref "U3") (pin "8") (pinfunction "PH_8") (pintype "passive"))
    )
    (net (code "80") (name "Net-(D4-K)") (class "Default")
      (node (ref "D4") (pin "2") (pinfunction "K_2") (pintype "passive"))
      (node (ref "U1") (pin "1") (pinfunction "5V_1") (pintype "passive"))
      (node (ref "U1") (pin "2") (pinfunction "5V_2") (pintype "passive"))
    )
    (net (code "81") (name "Net-(P3-Pad2)") (class "Default")
      (node (ref "P3") (pin "2") (pinfunction "2_2") (pintype "passive"))
      (node (ref "R20") (pin "1") (pinfunction "1_1") (pintype "passive"))
      (node (ref "SW1") (pin "2") (pinfunction "2_2") (pintype "passive"))
    )
    (net (code "82") (name "Net-(Q1-G)") (class "Default")
      (node (ref "Q1") (pin "1") (pinfunction "G_1") (pintype "passive"))
      (node (ref "R16") (pin "2") (pinfunction "2_2") (pintype "passive"))
    )
    (net (code "83") (name "Net-(U1-Boot0)") (class "Default")
      (node (ref "U1") (pin "89") (pinfunction "Boot0_89") (pintype "passive"))
      (node (ref "U1") (pin "91") (pinfunction "GND_91") (pintype "passive"))
    )
    (net (code "84") (name "Net-(U2-MD0)") (class "Default")
      (node (ref "R18") (pin "2") (pinfunction "2_2") (pintype "passive"))
      (node (ref "U2") (pin "1") (pinfunction "MD0_1") (pintype "passive"))
    )
    (net (code "85") (name "Net-(U3-BOOT)") (class "Default")
      (node (ref "C7") (pin "2") (pinfunction "2_2") (pintype "passive"))
      (node (ref "U3") (pin "1") (pinfunction "BOOT_1") (pintype "passive"))
    )
    (net (code "86") (name "Net-(U3-COMP)") (class "Default")
      (node (ref "C5") (pin "2") (pinfunction "2_2") (pintype "passive"))
      (node (ref "C6") (pin "2") (pinfunction "2_2") (pintype "passive"))
      (node (ref "U3") (pin "6") (pinfunction "COMP_6") (pintype "passive"))
    )
    (net (code "87") (name "Net-(U3-EN)") (class "Default")
      (node (ref "R1") (pin "2") (pinfunction "2_2") (pintype "passive"))
      (node (ref "R2") (pin "2") (pinfunction "2_2") (pintype "passive"))
      (node (ref "U3") (pin "3") (pinfunction "EN_3") (pintype "passive"))
    )
    (net (code "88") (name "Net-(U3-SS)") (class "Default")
      (node (ref "C4") (pin "2") (pinfunction "2_2") (pintype "passive"))
      (node (ref "U3") (pin "4") (pinfunction "SS_4") (pintype "passive"))
    )
    (net (code "89") (name "Net-(U3-VSENSE)") (class "Default")
      (node (ref "R4") (pin "1") (pinfunction "1_1") (pintype "passive"))
      (node (ref "R5") (pin "2") (pinfunction "2_2") (pintype "passive"))
      (node (ref "U3") (pin "5") (pinfunction "VSENSE_5") (pintype "passive"))
    )
    (net (code "90") (name "VM") (class "Default")
      (node (ref "C1") (pin "2") (pinfunction "2_2") (pintype "passive"))
      (node (ref "C2") (pin "2") (pinfunction "2_2") (pintype "passive"))
      (node (ref "C3") (pin "2") (pinfunction "2_2") (pintype "passive"))
      (node (ref "D3") (pin "2") (pinfunction "K_2") (pintype "passive"))
      (node (ref "R1") (pin "1") (pinfunction "1_1") (pintype "passive"))
      (node (ref "SW1") (pin "1") (pinfunction "1_1") (pintype "passive"))
      (node (ref "U3") (pin "2") (pinfunction "VIN_2") (pintype "passive"))
    )
    (net (code "91") (name "unconnected-(P2-FMARK-Pad8)") (class "Default")
      (node (ref "P2") (pin "8") (pinfunction "FMARK_8") (pintype "passive+no_connect"))
    )
    (net (code "92") (name "unconnected-(P2-SPI_SDA-Pad13)") (class "Default")
      (node (ref "P2") (pin "13") (pinfunction "SPI_SDA_13") (pintype "passive+no_connect"))
    )
    (net (code "93") (name "unconnected-(P2-SPI_SDO-Pad14)") (class "Default")
      (node (ref "P2") (pin "14") (pinfunction "SPI_SDO_14") (pintype "passive+no_connect"))
    )
    (net (code "94") (name "unconnected-(P2-XL(X-)-Pad1)") (class "Default")
      (node (ref "P2") (pin "1") (pinfunction "XL(X-)_1") (pintype "passive+no_connect"))
    )
    (net (code "95") (name "unconnected-(P2-XR(X+)-Pad3)") (class "Default")
      (node (ref "P2") (pin "3") (pinfunction "XR(X+)_3") (pintype "passive+no_connect"))
    )
    (net (code "96") (name "unconnected-(P2-YD(Y+)-Pad4)") (class "Default")
      (node (ref "P2") (pin "4") (pinfunction "YD(Y+)_4") (pintype "passive+no_connect"))
    )
    (net (code "97") (name "unconnected-(P2-YU(Y-)-Pad2)") (class "Default")
      (node (ref "P2") (pin "2") (pinfunction "YU(Y-)_2") (pintype "passive+no_connect"))
    )
    (net (code "98") (name "unconnected-(P3-Pad3)") (class "Default")
      (node (ref "P3") (pin "3") (pinfunction "3_3") (pintype "passive+no_connect"))
    )
    (net (code "99") (name "unconnected-(P3-Pad4)") (class "Default")
      (node (ref "P3") (pin "4") (pinfunction "4_4") (pintype "passive+no_connect"))
    )
    (net (code "100") (name "unconnected-(RP1-EH-Pad0)") (class "Default")
      (node (ref "RP1") (pin "0") (pinfunction "EH_0") (pintype "passive+no_connect"))
    )
    (net (code "101") (name "unconnected-(RP1-EH-Pad0)_1") (class "Default")
      (node (ref "RP1") (pin "0") (pinfunction "EH_0") (pintype "passive+no_connect"))
    )
    (net (code "102") (name "unconnected-(RP2-EH-Pad0)") (class "Default")
      (node (ref "RP2") (pin "0") (pinfunction "EH_0") (pintype "passive+no_connect"))
    )
    (net (code "103") (name "unconnected-(RP2-EH-Pad0)_1") (class "Default")
      (node (ref "RP2") (pin "0") (pinfunction "EH_0") (pintype "passive+no_connect"))
    )
    (net (code "104") (name "unconnected-(SW1-Pad3)") (class "Default")
      (node (ref "SW1") (pin "3") (pinfunction "3_3") (pintype "passive+no_connect"))
    )
    (net (code "105") (name "unconnected-(U1-3V3-Pad90)") (class "Default")
      (node (ref "U1") (pin "90") (pinfunction "3V3_90") (pintype "passive+no_connect"))
    )
    (net (code "106") (name "unconnected-(U1-PA15-Pad23)") (class "Default")
      (node (ref "U1") (pin "23") (pinfunction "PA15_23") (pintype "passive+no_connect"))
    )
    (net (code "107") (name "unconnected-(U1-PB12-Pad54)") (class "Default")
      (node (ref "U1") (pin "54") (pinfunction "PB12_54") (pintype "passive+no_connect"))
    )
    (net (code "108") (name "unconnected-(U1-PB13-Pad53)") (class "Default")
      (node (ref "U1") (pin "53") (pinfunction "PB13_53") (pintype "passive+no_connect"))
    )
    (net (code "109") (name "unconnected-(U1-PB14-Pad52)") (class "Default")
      (node (ref "U1") (pin "52") (pinfunction "PB14_52") (pintype "passive+no_connect"))
    )
    (net (code "110") (name "unconnected-(U1-PB15-Pad51)") (class "Default")
      (node (ref "U1") (pin "51") (pinfunction "PB15_51") (pintype "passive+no_connect"))
    )
    (net (code "111") (name "unconnected-(U1-PD11-Pad9)") (class "Default")
      (node (ref "U1") (pin "9") (pinfunction "PD11_9") (pintype "passive+no_connect"))
    )
    (net (code "112") (name "unconnected-(U1-PD12-Pad12)") (class "Default")
      (node (ref "U1") (pin "12") (pinfunction "PD12_12") (pintype "passive+no_connect"))
    )
    (net (code "113") (name "unconnected-(U1-PD13-Pad11)") (class "Default")
      (node (ref "U1") (pin "11") (pinfunction "PD13_11") (pintype "passive+no_connect"))
    )
    (net (code "114") (name "unconnected-(U1-VBAT+-Pad94)") (class "Default")
      (node (ref "U1") (pin "94") (pinfunction "VBAT+_94") (pintype "passive+no_connect"))
    )
    (net (code "115") (name "unconnected-(U1-VBAT--Pad95)") (class "Default")
      (node (ref "U1") (pin "95") (pinfunction "VBAT-_95") (pintype "passive+no_connect"))
    )
    (net (code "116") (name "unconnected-(U1-VDDA-Pad49)") (class "Default")
      (node (ref "U1") (pin "49") (pinfunction "VDDA_49") (pintype "passive+no_connect"))
    )
    (net (code "117") (name "unconnected-(U1-VREF+-Pad50)") (class "Default")
      (node (ref "U1") (pin "50") (pinfunction "VREF+_50") (pintype "passive+no_connect"))
    )
    (net (code "118") (name "unconnected-(U2-AUX-Pad5)") (class "Default")
      (node (ref "U2") (pin "5") (pinfunction "AUX_5") (pintype "passive+no_connect"))
    )
    (net (code "119") (name "unconnected-(U2-NC-Pad0)") (class "Default")
      (node (ref "U2") (pin "0") (pinfunction "NC_0") (pintype "passive+no_connect"))
    )
    (net (code "120") (name "unconnected-(U5-ECL-Pad6)") (class "Default")
      (node (ref "U5") (pin "6") (pinfunction "ECL_6") (pintype "passive+no_connect"))
    )
    (net (code "121") (name "unconnected-(U5-EDA-Pad5)") (class "Default")
      (node (ref "U5") (pin "5") (pinfunction "EDA_5") (pintype "passive+no_connect"))
    )
    (net (code "122") (name "unconnected-(U5-INT-Pad8)") (class "Default")
      (node (ref "U5") (pin "8") (pinfunction "INT_8") (pintype "passive+no_connect"))
    )
    (net (code "123") (name "unconnected-(U7-EP-Pad6)") (class "Default")
      (node (ref "U7") (pin "6") (pinfunction "EP_6") (pintype "passive+no_connect"))
    )
    (net (code "124") (name "unconnected-(U7-EP-Pad7)") (class "Default")
      (node (ref "U7") (pin "7") (pinfunction "EP_7") (pintype "passive+no_connect"))
    )
  )
)
